# ftdiusb.net
KiCad netlist of a schematic drawn in EAGLE
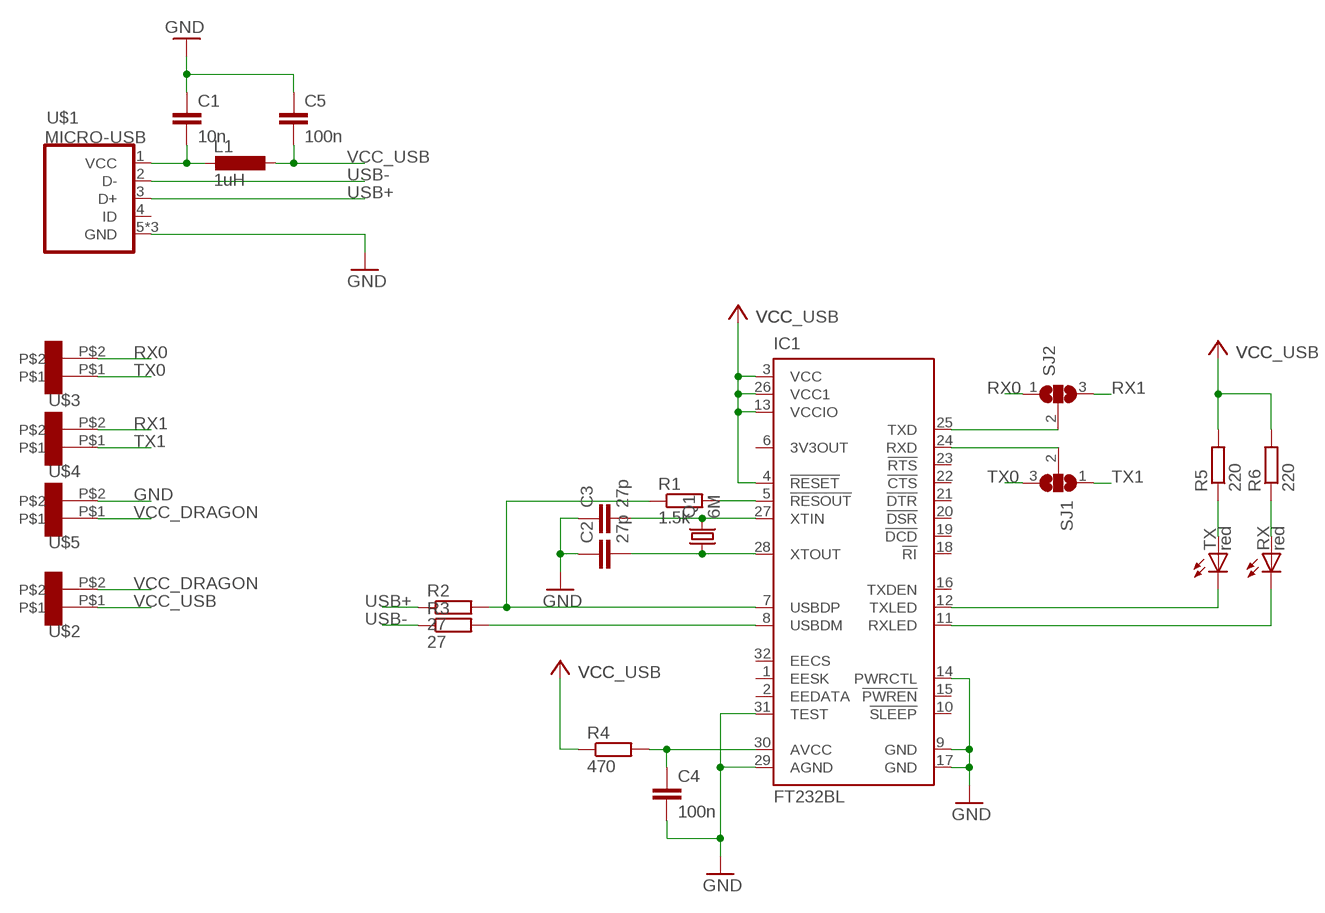
[diagram p0: schematic, sheet 1]

(export (version "E")
  (design (tool "Eeschema 10.0.6"))
  (components
    (comp (ref "C1")
      (value "10n")
      (footprint "eagle-import:C0603")
      (libsource (lib "eagle-import") (part "C-EUC0603"))
    )
    (comp (ref "C2")
      (value "27p")
      (footprint "eagle-import:C0603")
      (libsource (lib "eagle-import") (part "C-EUC0603"))
    )
    (comp (ref "C3")
      (value "27p")
      (footprint "eagle-import:C0603")
      (libsource (lib "eagle-import") (part "C-EUC0603"))
    )
    (comp (ref "C4")
      (value "100n")
      (footprint "eagle-import:C0603")
      (libsource (lib "eagle-import") (part "C-EUC0603"))
    )
    (comp (ref "C5")
      (value "100n")
      (footprint "eagle-import:C0603")
      (libsource (lib "eagle-import") (part "C-EUC0603"))
    )
    (comp (ref "IC1")
      (value "FT232BL")
      (footprint "eagle-import:LQFP32-7X7")
      (fields (field (name "MF") "FARNELL") (field (name "MPN") "FT232BL/TR"))
      (libsource (lib "eagle-import") (part "FT232BL"))
    )
    (comp (ref "L1")
      (value "1uH")
      (footprint "eagle-import:L0603")
      (libsource (lib "eagle-import") (part "L-EUL0603"))
    )
    (comp (ref "Q1")
      (value "6M")
      (footprint "eagle-import:HC49U-V")
      (libsource (lib "eagle-import") (part "CRYSTALHC49U-V"))
    )
    (comp (ref "R1")
      (value "1.5k")
      (footprint "eagle-import:R0603")
      (libsource (lib "eagle-import") (part "R-EU_R0603"))
    )
    (comp (ref "R2")
      (value "27")
      (footprint "eagle-import:R0603")
      (libsource (lib "eagle-import") (part "R-EU_R0603"))
    )
    (comp (ref "R3")
      (value "27")
      (footprint "eagle-import:R0603")
      (libsource (lib "eagle-import") (part "R-EU_R0603"))
    )
    (comp (ref "R4")
      (value "470")
      (footprint "eagle-import:R0603")
      (libsource (lib "eagle-import") (part "R-EU_R0603"))
    )
    (comp (ref "R5")
      (value "220")
      (footprint "eagle-import:R0603")
      (libsource (lib "eagle-import") (part "R-EU_R0603"))
    )
    (comp (ref "R6")
      (value "220")
      (footprint "eagle-import:R0603")
      (libsource (lib "eagle-import") (part "R-EU_R0603"))
    )
    (comp (ref "RX")
      (value "red")
      (footprint "eagle-import:C0603")
      (libsource (lib "eagle-import") (part "LED_0603"))
    )
    (comp (ref "SJ1")
      (value "SJ2WW")
      (footprint "eagle-import:SJ_2W")
      (libsource (lib "eagle-import") (part "SJ2WW"))
    )
    (comp (ref "SJ2")
      (value "SJ2WW")
      (footprint "eagle-import:SJ_2W")
      (libsource (lib "eagle-import") (part "SJ2WW"))
    )
    (comp (ref "TX")
      (value "red")
      (footprint "eagle-import:C0603")
      (libsource (lib "eagle-import") (part "LED_0603"))
    )
    (comp (ref "U$1")
      (value "MICRO-USB")
      (footprint "eagle-import:MICRO-USB")
      (libsource (lib "eagle-import") (part "MICRO-USB"))
    )
    (comp (ref "U$2")
      (value "CON_DIL_2")
      (footprint "eagle-import:CON_DIL_2")
      (libsource (lib "eagle-import") (part "CON_DIL_2"))
    )
    (comp (ref "U$3")
      (value "CON_DIL_2")
      (footprint "eagle-import:CON_DIL_2")
      (libsource (lib "eagle-import") (part "CON_DIL_2"))
    )
    (comp (ref "U$4")
      (value "CON_DIL_2")
      (footprint "eagle-import:CON_DIL_2")
      (libsource (lib "eagle-import") (part "CON_DIL_2"))
    )
    (comp (ref "U$5")
      (value "CON_DIL_2")
      (footprint "eagle-import:CON_DIL_2")
      (libsource (lib "eagle-import") (part "CON_DIL_2"))
    )
  )
  (nets
    (net (code "1") (name "/RX0") (class "Default")
      (node (ref "SJ2") (pin "1") (pinfunction "1_1") (pintype "passive"))
      (node (ref "U$3") (pin "P$2") (pinfunction "P$2_P$2") (pintype "bidirectional"))
    )
    (net (code "2") (name "/RX1") (class "Default")
      (node (ref "SJ2") (pin "3") (pinfunction "3_3") (pintype "passive"))
      (node (ref "U$4") (pin "P$2") (pinfunction "P$2_P$2") (pintype "bidirectional"))
    )
    (net (code "3") (name "/TX0") (class "Default")
      (node (ref "SJ1") (pin "3") (pinfunction "3_3") (pintype "passive"))
      (node (ref "U$3") (pin "P$1") (pinfunction "P$1_P$1") (pintype "bidirectional"))
    )
    (net (code "4") (name "/TX1") (class "Default")
      (node (ref "SJ1") (pin "1") (pinfunction "1_1") (pintype "passive"))
      (node (ref "U$4") (pin "P$1") (pinfunction "P$1_P$1") (pintype "bidirectional"))
    )
    (net (code "5") (name "/USB+") (class "Default")
      (node (ref "R2") (pin "1") (pinfunction "1_1") (pintype "passive"))
      (node (ref "U$1") (pin "3") (pinfunction "D+_3") (pintype "bidirectional"))
    )
    (net (code "6") (name "/USB-") (class "Default")
      (node (ref "R3") (pin "1") (pinfunction "1_1") (pintype "passive"))
      (node (ref "U$1") (pin "2") (pinfunction "D-_2") (pintype "bidirectional"))
    )
    (net (code "7") (name "/VCC_DRAGON") (class "Default")
      (node (ref "U$2") (pin "P$2") (pinfunction "P$2_P$2") (pintype "bidirectional"))
      (node (ref "U$5") (pin "P$1") (pinfunction "P$1_P$1") (pintype "bidirectional"))
    )
    (net (code "8") (name "GND") (class "Default")
      (node (ref "C1") (pin "1") (pinfunction "1_1") (pintype "passive"))
      (node (ref "C2") (pin "1") (pinfunction "1_1") (pintype "passive"))
      (node (ref "C3") (pin "1") (pinfunction "1_1") (pintype "passive"))
      (node (ref "C4") (pin "2") (pinfunction "2_2") (pintype "passive"))
      (node (ref "C5") (pin "1") (pinfunction "1_1") (pintype "passive"))
      (node (ref "IC1") (pin "14") (pinfunction "PWRCTL_14") (pintype "bidirectional"))
      (node (ref "IC1") (pin "17") (pinfunction "GND_17") (pintype "power_in"))
      (node (ref "IC1") (pin "29") (pinfunction "AGND_29") (pintype "power_in"))
      (node (ref "IC1") (pin "31") (pinfunction "TEST_31") (pintype "input"))
      (node (ref "IC1") (pin "9") (pinfunction "GND_9") (pintype "power_in"))
      (node (ref "U$1") (pin "5") (pinfunction "GND_5") (pintype "power_in"))
      (node (ref "U$1") (pin "GND1") (pinfunction "GND_GND1") (pintype "power_in"))
      (node (ref "U$1") (pin "GND2") (pinfunction "GND_GND2") (pintype "power_in"))
      (node (ref "U$5") (pin "P$2") (pinfunction "P$2_P$2") (pintype "bidirectional"))
    )
    (net (code "9") (name "Net-(IC1-AVCC)") (class "Default")
      (node (ref "C4") (pin "1") (pinfunction "1_1") (pintype "passive"))
      (node (ref "IC1") (pin "30") (pinfunction "AVCC_30") (pintype "power_in"))
      (node (ref "R4") (pin "2") (pinfunction "2_2") (pintype "passive"))
    )
    (net (code "10") (name "Net-(IC1-RXD)") (class "Default")
      (node (ref "IC1") (pin "24") (pinfunction "RXD_24") (pintype "input"))
      (node (ref "SJ1") (pin "2") (pinfunction "2_2") (pintype "passive"))
    )
    (net (code "11") (name "Net-(IC1-RXLED)") (class "Default")
      (node (ref "IC1") (pin "11") (pinfunction "RXLED_11") (pintype "bidirectional"))
      (node (ref "RX") (pin "N") (pinfunction "N_N") (pintype "passive"))
    )
    (net (code "12") (name "Net-(IC1-TXD)") (class "Default")
      (node (ref "IC1") (pin "25") (pinfunction "TXD_25") (pintype "output"))
      (node (ref "SJ2") (pin "2") (pinfunction "2_2") (pintype "passive"))
    )
    (net (code "13") (name "Net-(IC1-TXLED)") (class "Default")
      (node (ref "IC1") (pin "12") (pinfunction "TXLED_12") (pintype "bidirectional"))
      (node (ref "TX") (pin "N") (pinfunction "N_N") (pintype "passive"))
    )
    (net (code "14") (name "Net-(IC1-USBDM)") (class "Default")
      (node (ref "IC1") (pin "8") (pinfunction "USBDM_8") (pintype "bidirectional"))
      (node (ref "R3") (pin "2") (pinfunction "2_2") (pintype "passive"))
    )
    (net (code "15") (name "Net-(IC1-USBDP)") (class "Default")
      (node (ref "IC1") (pin "7") (pinfunction "USBDP_7") (pintype "bidirectional"))
      (node (ref "R1") (pin "1") (pinfunction "1_1") (pintype "passive"))
      (node (ref "R2") (pin "2") (pinfunction "2_2") (pintype "passive"))
    )
    (net (code "16") (name "Net-(IC1-XTIN)") (class "Default")
      (node (ref "C3") (pin "2") (pinfunction "2_2") (pintype "passive"))
      (node (ref "IC1") (pin "27") (pinfunction "XTIN_27") (pintype "input"))
      (node (ref "Q1") (pin "2") (pinfunction "2_2") (pintype "passive"))
    )
    (net (code "17") (name "Net-(IC1-XTOUT)") (class "Default")
      (node (ref "C2") (pin "2") (pinfunction "2_2") (pintype "passive"))
      (node (ref "IC1") (pin "28") (pinfunction "XTOUT_28") (pintype "output"))
      (node (ref "Q1") (pin "1") (pinfunction "1_1") (pintype "passive"))
    )
    (net (code "18") (name "Net-(IC1-~{RESOUT})") (class "Default")
      (node (ref "IC1") (pin "5") (pinfunction "~{RESOUT}_5") (pintype "input"))
      (node (ref "R1") (pin "2") (pinfunction "2_2") (pintype "passive"))
    )
    (net (code "19") (name "Net-(R5-Pad1)") (class "Default")
      (node (ref "R5") (pin "1") (pinfunction "1_1") (pintype "passive"))
      (node (ref "TX") (pin "P") (pinfunction "P_P") (pintype "passive"))
    )
    (net (code "20") (name "Net-(R6-Pad1)") (class "Default")
      (node (ref "R6") (pin "1") (pinfunction "1_1") (pintype "passive"))
      (node (ref "RX") (pin "P") (pinfunction "P_P") (pintype "passive"))
    )
    (net (code "21") (name "Net-(U$1-VCC)") (class "Default")
      (node (ref "C1") (pin "2") (pinfunction "2_2") (pintype "passive"))
      (node (ref "L1") (pin "2") (pinfunction "2_2") (pintype "passive"))
      (node (ref "U$1") (pin "1") (pinfunction "VCC_1") (pintype "power_in"))
    )
    (net (code "22") (name "VCC") (class "Default")
      (node (ref "C5") (pin "2") (pinfunction "2_2") (pintype "passive"))
      (node (ref "IC1") (pin "13") (pinfunction "VCCIO_13") (pintype "power_in"))
      (node (ref "IC1") (pin "26") (pinfunction "VCC1_26") (pintype "power_in"))
      (node (ref "IC1") (pin "3") (pinfunction "VCC_3") (pintype "power_in"))
      (node (ref "IC1") (pin "4") (pinfunction "~{RESET}_4") (pintype "input"))
      (node (ref "L1") (pin "1") (pinfunction "1_1") (pintype "passive"))
      (node (ref "R4") (pin "1") (pinfunction "1_1") (pintype "passive"))
      (node (ref "R5") (pin "2") (pinfunction "2_2") (pintype "passive"))
      (node (ref "R6") (pin "2") (pinfunction "2_2") (pintype "passive"))
      (node (ref "U$2") (pin "P$1") (pinfunction "P$1_P$1") (pintype "bidirectional"))
    )
    (net (code "23") (name "unconnected-(IC1-3V3OUT-Pad6)") (class "Default")
      (node (ref "IC1") (pin "6") (pinfunction "3V3OUT_6") (pintype "output"))
    )
    (net (code "24") (name "unconnected-(IC1-EECS-Pad32)") (class "Default")
      (node (ref "IC1") (pin "32") (pinfunction "EECS_32") (pintype "input"))
    )
    (net (code "25") (name "unconnected-(IC1-EEDATA-Pad2)") (class "Default")
      (node (ref "IC1") (pin "2") (pinfunction "EEDATA_2") (pintype "input"))
    )
    (net (code "26") (name "unconnected-(IC1-EESK-Pad1)") (class "Default")
      (node (ref "IC1") (pin "1") (pinfunction "EESK_1") (pintype "input"))
    )
    (net (code "27") (name "unconnected-(IC1-TXDEN-Pad16)") (class "Default")
      (node (ref "IC1") (pin "16") (pinfunction "TXDEN_16") (pintype "bidirectional"))
    )
    (net (code "28") (name "unconnected-(IC1-~{CTS}-Pad22)") (class "Default")
      (node (ref "IC1") (pin "22") (pinfunction "~{CTS}_22") (pintype "input"))
    )
    (net (code "29") (name "unconnected-(IC1-~{DCD}-Pad19)") (class "Default")
      (node (ref "IC1") (pin "19") (pinfunction "~{DCD}_19") (pintype "input"))
    )
    (net (code "30") (name "unconnected-(IC1-~{DSR}-Pad20)") (class "Default")
      (node (ref "IC1") (pin "20") (pinfunction "~{DSR}_20") (pintype "input"))
    )
    (net (code "31") (name "unconnected-(IC1-~{DTR}-Pad21)") (class "Default")
      (node (ref "IC1") (pin "21") (pinfunction "~{DTR}_21") (pintype "output"))
    )
    (net (code "32") (name "unconnected-(IC1-~{PWREN}-Pad15)") (class "Default")
      (node (ref "IC1") (pin "15") (pinfunction "~{PWREN}_15") (pintype "bidirectional"))
    )
    (net (code "33") (name "unconnected-(IC1-~{RI}-Pad18)") (class "Default")
      (node (ref "IC1") (pin "18") (pinfunction "~{RI}_18") (pintype "input"))
    )
    (net (code "34") (name "unconnected-(IC1-~{RTS}-Pad23)") (class "Default")
      (node (ref "IC1") (pin "23") (pinfunction "~{RTS}_23") (pintype "output"))
    )
    (net (code "35") (name "unconnected-(IC1-~{SLEEP}-Pad10)") (class "Default")
      (node (ref "IC1") (pin "10") (pinfunction "~{SLEEP}_10") (pintype "input"))
    )
    (net (code "36") (name "unconnected-(U$1-ID-Pad4)") (class "Default")
      (node (ref "U$1") (pin "4") (pinfunction "ID_4") (pintype "bidirectional"))
    )
  )
)
